# Mini_1284.net
KiCad netlist of a schematic drawn in EAGLE
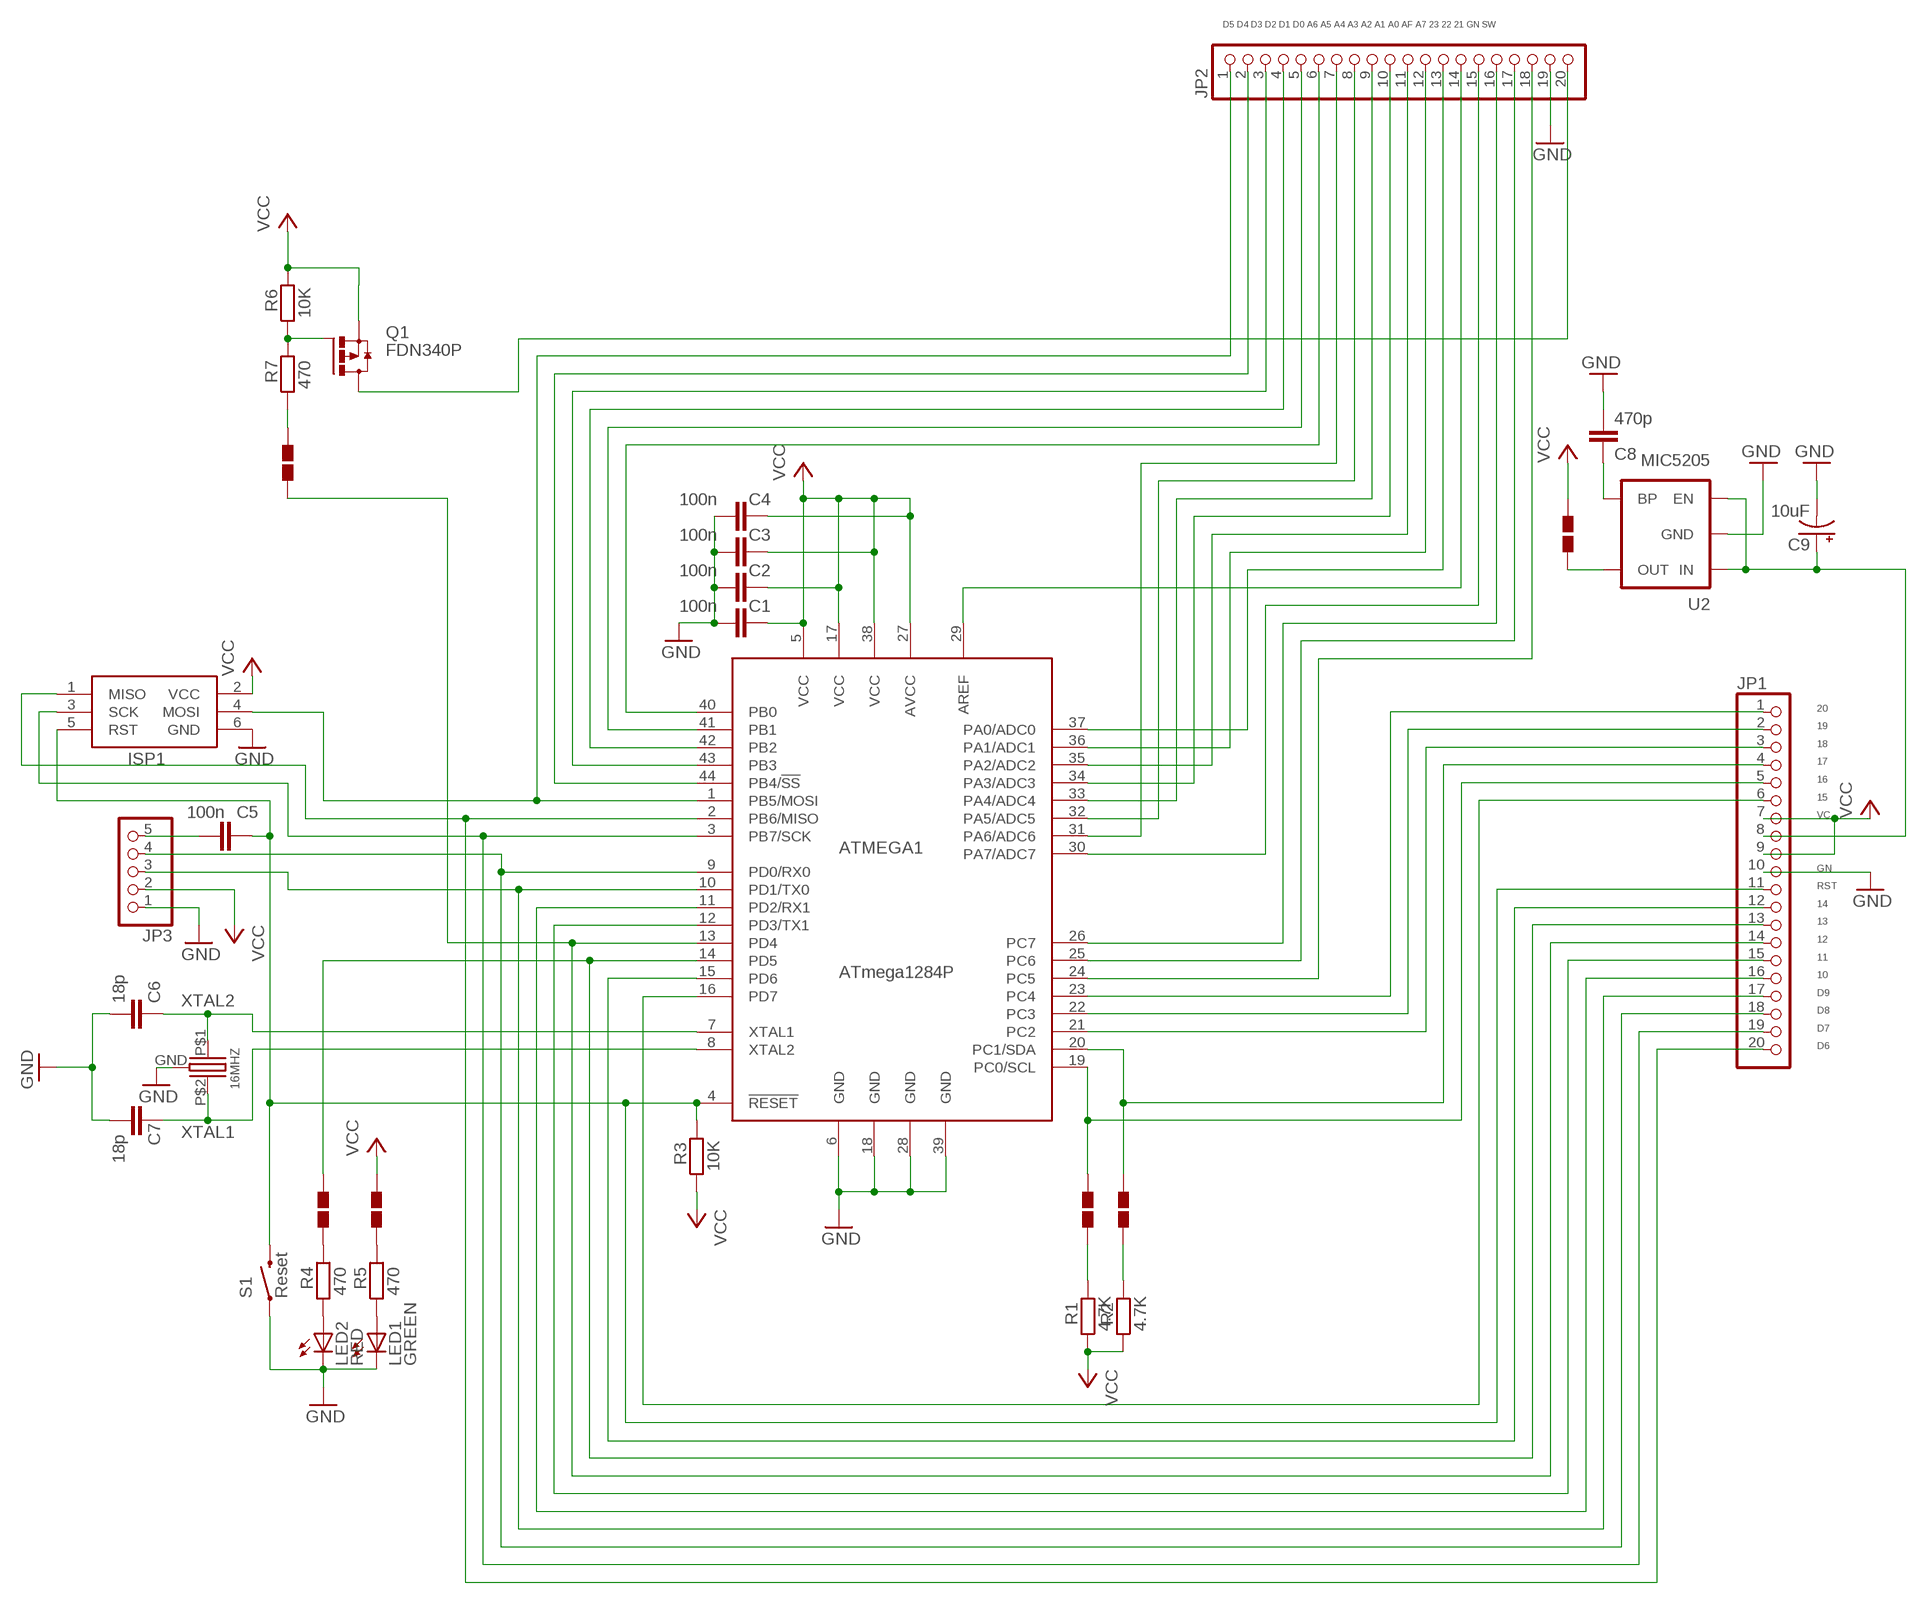
[diagram p0: schematic, sheet 1]

(export (version "E")
  (design (tool "Eeschema 10.0.6"))
  (components
    (comp (ref "16MHZ")
      (value "CX2520")
      (footprint "eagle-import:CX2520")
      (libsource (lib "eagle-import") (part "CX2520"))
    )
    (comp (ref "ATMEGA1")
      (value "ATmega1284P")
      (footprint "eagle-import:44TQFP")
      (libsource (lib "eagle-import") (part "ATMEGA164A/PA/324A/PA/644A/PA/1284/P"))
    )
    (comp (ref "C1")
      (value "100n")
      (footprint "eagle-import:C0603-ROUND")
      (libsource (lib "eagle-import") (part "C0603-ROUND"))
    )
    (comp (ref "C2")
      (value "100n")
      (footprint "eagle-import:C0603-ROUND")
      (libsource (lib "eagle-import") (part "C0603-ROUND"))
    )
    (comp (ref "C3")
      (value "100n")
      (footprint "eagle-import:C0603-ROUND")
      (libsource (lib "eagle-import") (part "C0603-ROUND"))
    )
    (comp (ref "C4")
      (value "100n")
      (footprint "eagle-import:C0603-ROUND")
      (libsource (lib "eagle-import") (part "C0603-ROUND"))
    )
    (comp (ref "C5")
      (value "100n")
      (footprint "eagle-import:C0603-ROUND")
      (libsource (lib "eagle-import") (part "C0603-ROUND"))
    )
    (comp (ref "C6")
      (value "18p")
      (footprint "eagle-import:C0603-ROUND")
      (libsource (lib "eagle-import") (part "C0603-ROUND"))
    )
    (comp (ref "C7")
      (value "18p")
      (footprint "eagle-import:C0603-ROUND")
      (libsource (lib "eagle-import") (part "C0603-ROUND"))
    )
    (comp (ref "C8")
      (value "470p")
      (footprint "eagle-import:C0603-ROUND")
      (libsource (lib "eagle-import") (part "C0603-ROUND"))
    )
    (comp (ref "C9")
      (value "10uF")
      (footprint "eagle-import:EIA3216")
      (libsource (lib "eagle-import") (part "CAP_POL1206"))
    )
    (comp (ref "ISP1")
      (value "AVRISP-6")
      (footprint "eagle-import:AVRISP")
      (libsource (lib "eagle-import") (part "AVRISP-6"))
    )
    (comp (ref "JP1")
      (value "PINHD-1X20")
      (footprint "eagle-import:1X20")
      (libsource (lib "eagle-import") (part "PINHD-1X20"))
    )
    (comp (ref "JP2")
      (value "PINHD-1X20")
      (footprint "eagle-import:1X20")
      (libsource (lib "eagle-import") (part "PINHD-1X20"))
    )
    (comp (ref "JP3")
      (value "PINHD-1X5")
      (footprint "eagle-import:1X05")
      (libsource (lib "eagle-import") (part "PINHD-1X5"))
    )
    (comp (ref "LED1")
      (value "GREEN")
      (footprint "eagle-import:CHIP-LED0805")
      (libsource (lib "eagle-import") (part "LEDCHIP-LED0805"))
    )
    (comp (ref "LED2")
      (value "RED")
      (footprint "eagle-import:CHIP-LED0805")
      (libsource (lib "eagle-import") (part "LEDCHIP-LED0805"))
    )
    (comp (ref "Q1")
      (value "FDN340P")
      (footprint "eagle-import:SUPER-SOT3")
      (libsource (lib "eagle-import") (part "FDN360P"))
    )
    (comp (ref "R1")
      (value "4.7K")
      (footprint "eagle-import:R0603-ROUND")
      (libsource (lib "eagle-import") (part "R0603-ROUND"))
    )
    (comp (ref "R2")
      (value "4.7K")
      (footprint "eagle-import:R0603-ROUND")
      (libsource (lib "eagle-import") (part "R0603-ROUND"))
    )
    (comp (ref "R3")
      (value "10K")
      (footprint "eagle-import:R0603-ROUND")
      (libsource (lib "eagle-import") (part "R0603-ROUND"))
    )
    (comp (ref "R4")
      (value "470")
      (footprint "eagle-import:R0603-ROUND")
      (libsource (lib "eagle-import") (part "R0603-ROUND"))
    )
    (comp (ref "R5")
      (value "470")
      (footprint "eagle-import:R0603-ROUND")
      (libsource (lib "eagle-import") (part "R0603-ROUND"))
    )
    (comp (ref "R6")
      (value "10K")
      (footprint "eagle-import:R0603-ROUND")
      (libsource (lib "eagle-import") (part "R0603-ROUND"))
    )
    (comp (ref "R7")
      (value "470")
      (footprint "eagle-import:R0603-ROUND")
      (libsource (lib "eagle-import") (part "R0603-ROUND"))
    )
    (comp (ref "S1")
      (value "Reset")
      (footprint "eagle-import:TACTILE-SWITCH-SMD-ALT01")
      (libsource (lib "eagle-import") (part "SWITCH-MOMENTARY-2SMD-ALT01"))
    )
    (comp (ref "U$4")
      (value "SOL-PAD-OPEN")
      (footprint "eagle-import:SOL-PAD-OPEN")
      (libsource (lib "eagle-import") (part "SOL-PAD-OPEN"))
    )
    (comp (ref "U$5")
      (value "SOL-PAD-OPEN")
      (footprint "eagle-import:SOL-PAD-OPEN")
      (libsource (lib "eagle-import") (part "SOL-PAD-OPEN"))
    )
    (comp (ref "U$8")
      (value "SOL-PAD-OPEN")
      (footprint "eagle-import:SOL-PAD-OPEN")
      (libsource (lib "eagle-import") (part "SOL-PAD-OPEN"))
    )
    (comp (ref "U$9")
      (value "SOL-PAD-OPEN")
      (footprint "eagle-import:SOL-PAD-OPEN")
      (libsource (lib "eagle-import") (part "SOL-PAD-OPEN"))
    )
    (comp (ref "U$12")
      (value "SOL-PAD-OPEN")
      (footprint "eagle-import:SOL-PAD-OPEN")
      (libsource (lib "eagle-import") (part "SOL-PAD-OPEN"))
    )
    (comp (ref "U$13")
      (value "SOL-PAD-OPEN")
      (footprint "eagle-import:SOL-PAD-OPEN")
      (libsource (lib "eagle-import") (part "SOL-PAD-OPEN"))
    )
    (comp (ref "U2")
      (value "MIC5205")
      (footprint "eagle-import:SOT23-5")
      (libsource (lib "eagle-import") (part "V_REG_LDOSMD"))
    )
  )
  (nets
    (net (code "1") (name "/XTAL1") (class "Default")
      (node (ref "16MHZ") (pin "P$2") (pinfunction "XTAL2_P$2") (pintype "bidirectional"))
      (node (ref "ATMEGA1") (pin "8") (pinfunction "XTAL2_8") (pintype "bidirectional"))
      (node (ref "C7") (pin "1") (pinfunction "1_1") (pintype "passive"))
    )
    (net (code "2") (name "/XTAL2") (class "Default")
      (node (ref "16MHZ") (pin "P$1") (pinfunction "XTAL1_P$1") (pintype "bidirectional"))
      (node (ref "ATMEGA1") (pin "7") (pinfunction "XTAL1_7") (pintype "bidirectional"))
      (node (ref "C6") (pin "1") (pinfunction "1_1") (pintype "passive"))
    )
    (net (code "3") (name "GND") (class "Default")
      (node (ref "16MHZ") (pin "GND") (pinfunction "GND_GND") (pintype "bidirectional"))
      (node (ref "ATMEGA1") (pin "18") (pinfunction "GND_18") (pintype "bidirectional"))
      (node (ref "ATMEGA1") (pin "28") (pinfunction "GND_28") (pintype "bidirectional"))
      (node (ref "ATMEGA1") (pin "39") (pinfunction "GND_39") (pintype "bidirectional"))
      (node (ref "ATMEGA1") (pin "6") (pinfunction "GND_6") (pintype "bidirectional"))
      (node (ref "C1") (pin "2") (pinfunction "2_2") (pintype "passive"))
      (node (ref "C2") (pin "2") (pinfunction "2_2") (pintype "passive"))
      (node (ref "C3") (pin "2") (pinfunction "2_2") (pintype "passive"))
      (node (ref "C4") (pin "2") (pinfunction "2_2") (pintype "passive"))
      (node (ref "C6") (pin "2") (pinfunction "2_2") (pintype "passive"))
      (node (ref "C7") (pin "2") (pinfunction "2_2") (pintype "passive"))
      (node (ref "C8") (pin "2") (pinfunction "2_2") (pintype "passive"))
      (node (ref "C9") (pin "C") (pinfunction "-_C") (pintype "passive"))
      (node (ref "ISP1") (pin "6") (pinfunction "GND_6") (pintype "power_in"))
      (node (ref "JP1") (pin "10") (pinfunction "10_10") (pintype "passive"))
      (node (ref "JP2") (pin "19") (pinfunction "19_19") (pintype "passive"))
      (node (ref "JP3") (pin "1") (pinfunction "1_1") (pintype "passive"))
      (node (ref "LED1") (pin "C") (pinfunction "C_C") (pintype "passive"))
      (node (ref "LED2") (pin "C") (pinfunction "C_C") (pintype "passive"))
      (node (ref "S1") (pin "1") (pinfunction "1_1") (pintype "passive"))
      (node (ref "S1") (pin "2") (pinfunction "1_2") (pintype "passive"))
      (node (ref "U2") (pin "2") (pinfunction "GND_2") (pintype "input"))
    )
    (net (code "4") (name "Net-(ATMEGA1-AREF)") (class "Default")
      (node (ref "ATMEGA1") (pin "29") (pinfunction "AREF_29") (pintype "bidirectional"))
      (node (ref "JP2") (pin "14") (pinfunction "14_14") (pintype "passive"))
    )
    (net (code "5") (name "Net-(ATMEGA1-PA0{slash}ADC0)") (class "Default")
      (node (ref "ATMEGA1") (pin "37") (pinfunction "PA0/ADC0_37") (pintype "bidirectional"))
      (node (ref "JP2") (pin "13") (pinfunction "13_13") (pintype "passive"))
    )
    (net (code "6") (name "Net-(ATMEGA1-PA1{slash}ADC1)") (class "Default")
      (node (ref "ATMEGA1") (pin "36") (pinfunction "PA1/ADC1_36") (pintype "bidirectional"))
      (node (ref "JP2") (pin "12") (pinfunction "12_12") (pintype "passive"))
    )
    (net (code "7") (name "Net-(ATMEGA1-PA2{slash}ADC2)") (class "Default")
      (node (ref "ATMEGA1") (pin "35") (pinfunction "PA2/ADC2_35") (pintype "bidirectional"))
      (node (ref "JP2") (pin "11") (pinfunction "11_11") (pintype "passive"))
    )
    (net (code "8") (name "Net-(ATMEGA1-PA3{slash}ADC3)") (class "Default")
      (node (ref "ATMEGA1") (pin "34") (pinfunction "PA3/ADC3_34") (pintype "bidirectional"))
      (node (ref "JP2") (pin "10") (pinfunction "10_10") (pintype "passive"))
    )
    (net (code "9") (name "Net-(ATMEGA1-PA4{slash}ADC4)") (class "Default")
      (node (ref "ATMEGA1") (pin "33") (pinfunction "PA4/ADC4_33") (pintype "bidirectional"))
      (node (ref "JP2") (pin "9") (pinfunction "9_9") (pintype "passive"))
    )
    (net (code "10") (name "Net-(ATMEGA1-PA5{slash}ADC5)") (class "Default")
      (node (ref "ATMEGA1") (pin "32") (pinfunction "PA5/ADC5_32") (pintype "bidirectional"))
      (node (ref "JP2") (pin "8") (pinfunction "8_8") (pintype "passive"))
    )
    (net (code "11") (name "Net-(ATMEGA1-PA6{slash}ADC6)") (class "Default")
      (node (ref "ATMEGA1") (pin "31") (pinfunction "PA6/ADC6_31") (pintype "bidirectional"))
      (node (ref "JP2") (pin "7") (pinfunction "7_7") (pintype "passive"))
    )
    (net (code "12") (name "Net-(ATMEGA1-PA7{slash}ADC7)") (class "Default")
      (node (ref "ATMEGA1") (pin "30") (pinfunction "PA7/ADC7_30") (pintype "bidirectional"))
      (node (ref "JP2") (pin "15") (pinfunction "15_15") (pintype "passive"))
    )
    (net (code "13") (name "Net-(ATMEGA1-PB0)") (class "Default")
      (node (ref "ATMEGA1") (pin "40") (pinfunction "PB0_40") (pintype "bidirectional"))
      (node (ref "JP2") (pin "6") (pinfunction "6_6") (pintype "passive"))
    )
    (net (code "14") (name "Net-(ATMEGA1-PB1)") (class "Default")
      (node (ref "ATMEGA1") (pin "41") (pinfunction "PB1_41") (pintype "bidirectional"))
      (node (ref "JP2") (pin "5") (pinfunction "5_5") (pintype "passive"))
    )
    (net (code "15") (name "Net-(ATMEGA1-PB2)") (class "Default")
      (node (ref "ATMEGA1") (pin "42") (pinfunction "PB2_42") (pintype "bidirectional"))
      (node (ref "JP2") (pin "4") (pinfunction "4_4") (pintype "passive"))
    )
    (net (code "16") (name "Net-(ATMEGA1-PB3)") (class "Default")
      (node (ref "ATMEGA1") (pin "43") (pinfunction "PB3_43") (pintype "bidirectional"))
      (node (ref "JP2") (pin "3") (pinfunction "3_3") (pintype "passive"))
    )
    (net (code "17") (name "Net-(ATMEGA1-PB4{slash}~{SS})") (class "Default")
      (node (ref "ATMEGA1") (pin "44") (pinfunction "PB4/~{SS}_44") (pintype "bidirectional"))
      (node (ref "JP2") (pin "2") (pinfunction "2_2") (pintype "passive"))
    )
    (net (code "18") (name "Net-(ATMEGA1-PB5{slash}MOSI)") (class "Default")
      (node (ref "ATMEGA1") (pin "1") (pinfunction "PB5/MOSI_1") (pintype "bidirectional"))
      (node (ref "ISP1") (pin "4") (pinfunction "MOSI_4") (pintype "output"))
      (node (ref "JP2") (pin "1") (pinfunction "1_1") (pintype "passive"))
    )
    (net (code "19") (name "Net-(ATMEGA1-PB6{slash}MISO)") (class "Default")
      (node (ref "ATMEGA1") (pin "2") (pinfunction "PB6/MISO_2") (pintype "bidirectional"))
      (node (ref "ISP1") (pin "1") (pinfunction "MISO_1") (pintype "input"))
      (node (ref "JP1") (pin "20") (pinfunction "20_20") (pintype "passive"))
    )
    (net (code "20") (name "Net-(ATMEGA1-PB7{slash}SCK)") (class "Default")
      (node (ref "ATMEGA1") (pin "3") (pinfunction "PB7/SCK_3") (pintype "bidirectional"))
      (node (ref "ISP1") (pin "3") (pinfunction "SCK_3") (pintype "output"))
      (node (ref "JP1") (pin "19") (pinfunction "19_19") (pintype "passive"))
    )
    (net (code "21") (name "Net-(ATMEGA1-PC0{slash}SCL)") (class "Default")
      (node (ref "ATMEGA1") (pin "19") (pinfunction "PC0/SCL_19") (pintype "bidirectional"))
      (node (ref "JP1") (pin "5") (pinfunction "5_5") (pintype "passive"))
      (node (ref "U$4") (pin "P$2") (pinfunction "2_P$2") (pintype "bidirectional"))
    )
    (net (code "22") (name "Net-(ATMEGA1-PC1{slash}SDA)") (class "Default")
      (node (ref "ATMEGA1") (pin "20") (pinfunction "PC1/SDA_20") (pintype "bidirectional"))
      (node (ref "JP1") (pin "4") (pinfunction "4_4") (pintype "passive"))
      (node (ref "U$12") (pin "P$1") (pinfunction "1_P$1") (pintype "bidirectional"))
    )
    (net (code "23") (name "Net-(ATMEGA1-PC2)") (class "Default")
      (node (ref "ATMEGA1") (pin "21") (pinfunction "PC2_21") (pintype "bidirectional"))
      (node (ref "JP1") (pin "3") (pinfunction "3_3") (pintype "passive"))
    )
    (net (code "24") (name "Net-(ATMEGA1-PC3)") (class "Default")
      (node (ref "ATMEGA1") (pin "22") (pinfunction "PC3_22") (pintype "bidirectional"))
      (node (ref "JP1") (pin "2") (pinfunction "2_2") (pintype "passive"))
    )
    (net (code "25") (name "Net-(ATMEGA1-PC4)") (class "Default")
      (node (ref "ATMEGA1") (pin "23") (pinfunction "PC4_23") (pintype "bidirectional"))
      (node (ref "JP1") (pin "1") (pinfunction "1_1") (pintype "passive"))
    )
    (net (code "26") (name "Net-(ATMEGA1-PC5)") (class "Default")
      (node (ref "ATMEGA1") (pin "24") (pinfunction "PC5_24") (pintype "bidirectional"))
      (node (ref "JP2") (pin "18") (pinfunction "18_18") (pintype "passive"))
    )
    (net (code "27") (name "Net-(ATMEGA1-PC6)") (class "Default")
      (node (ref "ATMEGA1") (pin "25") (pinfunction "PC6_25") (pintype "bidirectional"))
      (node (ref "JP2") (pin "17") (pinfunction "17_17") (pintype "passive"))
    )
    (net (code "28") (name "Net-(ATMEGA1-PC7)") (class "Default")
      (node (ref "ATMEGA1") (pin "26") (pinfunction "PC7_26") (pintype "bidirectional"))
      (node (ref "JP2") (pin "16") (pinfunction "16_16") (pintype "passive"))
    )
    (net (code "29") (name "Net-(ATMEGA1-PD0{slash}RX0)") (class "Default")
      (node (ref "ATMEGA1") (pin "9") (pinfunction "PD0/RX0_9") (pintype "bidirectional"))
      (node (ref "JP1") (pin "18") (pinfunction "18_18") (pintype "passive"))
      (node (ref "JP3") (pin "4") (pinfunction "4_4") (pintype "passive"))
    )
    (net (code "30") (name "Net-(ATMEGA1-PD1{slash}TX0)") (class "Default")
      (node (ref "ATMEGA1") (pin "10") (pinfunction "PD1/TX0_10") (pintype "bidirectional"))
      (node (ref "JP1") (pin "17") (pinfunction "17_17") (pintype "passive"))
      (node (ref "JP3") (pin "3") (pinfunction "3_3") (pintype "passive"))
    )
    (net (code "31") (name "Net-(ATMEGA1-PD2{slash}RX1)") (class "Default")
      (node (ref "ATMEGA1") (pin "11") (pinfunction "PD2/RX1_11") (pintype "bidirectional"))
      (node (ref "JP1") (pin "16") (pinfunction "16_16") (pintype "passive"))
    )
    (net (code "32") (name "Net-(ATMEGA1-PD3{slash}TX1)") (class "Default")
      (node (ref "ATMEGA1") (pin "12") (pinfunction "PD3/TX1_12") (pintype "bidirectional"))
      (node (ref "JP1") (pin "15") (pinfunction "15_15") (pintype "passive"))
    )
    (net (code "33") (name "Net-(ATMEGA1-PD4)") (class "Default")
      (node (ref "ATMEGA1") (pin "13") (pinfunction "PD4_13") (pintype "bidirectional"))
      (node (ref "JP1") (pin "14") (pinfunction "14_14") (pintype "passive"))
      (node (ref "U$5") (pin "P$1") (pinfunction "1_P$1") (pintype "bidirectional"))
    )
    (net (code "34") (name "Net-(ATMEGA1-PD5)") (class "Default")
      (node (ref "ATMEGA1") (pin "14") (pinfunction "PD5_14") (pintype "bidirectional"))
      (node (ref "JP1") (pin "13") (pinfunction "13_13") (pintype "passive"))
      (node (ref "U$9") (pin "P$2") (pinfunction "2_P$2") (pintype "bidirectional"))
    )
    (net (code "35") (name "Net-(ATMEGA1-PD6)") (class "Default")
      (node (ref "ATMEGA1") (pin "15") (pinfunction "PD6_15") (pintype "bidirectional"))
      (node (ref "JP1") (pin "12") (pinfunction "12_12") (pintype "passive"))
    )
    (net (code "36") (name "Net-(ATMEGA1-PD7)") (class "Default")
      (node (ref "ATMEGA1") (pin "16") (pinfunction "PD7_16") (pintype "bidirectional"))
      (node (ref "JP1") (pin "6") (pinfunction "6_6") (pintype "passive"))
    )
    (net (code "37") (name "Net-(ATMEGA1-~{RESET})") (class "Default")
      (node (ref "ATMEGA1") (pin "4") (pinfunction "~{RESET}_4") (pintype "bidirectional"))
      (node (ref "C5") (pin "1") (pinfunction "1_1") (pintype "passive"))
      (node (ref "ISP1") (pin "5") (pinfunction "RST_5") (pintype "output"))
      (node (ref "JP1") (pin "11") (pinfunction "11_11") (pintype "passive"))
      (node (ref "R3") (pin "2") (pinfunction "2_2") (pintype "passive"))
      (node (ref "S1") (pin "3") (pinfunction "2_3") (pintype "passive"))
      (node (ref "S1") (pin "4") (pinfunction "2_4") (pintype "passive"))
    )
    (net (code "38") (name "Net-(C5-Pad2)") (class "Default")
      (node (ref "C5") (pin "2") (pinfunction "2_2") (pintype "passive"))
      (node (ref "JP3") (pin "5") (pinfunction "5_5") (pintype "passive"))
    )
    (net (code "39") (name "Net-(C9-+)") (class "Default")
      (node (ref "C9") (pin "A") (pinfunction "+_A") (pintype "passive"))
      (node (ref "JP1") (pin "8") (pinfunction "8_8") (pintype "passive"))
      (node (ref "U2") (pin "1") (pinfunction "IN_1") (pintype "input"))
      (node (ref "U2") (pin "3") (pinfunction "EN_3") (pintype "input"))
    )
    (net (code "40") (name "Net-(LED1-PadA)") (class "Default")
      (node (ref "LED1") (pin "A") (pinfunction "A_A") (pintype "passive"))
      (node (ref "R5") (pin "1") (pinfunction "1_1") (pintype "passive"))
    )
    (net (code "41") (name "Net-(LED2-PadA)") (class "Default")
      (node (ref "LED2") (pin "A") (pinfunction "A_A") (pintype "passive"))
      (node (ref "R4") (pin "1") (pinfunction "1_1") (pintype "passive"))
    )
    (net (code "42") (name "Net-(Q1-D)") (class "Default")
      (node (ref "JP2") (pin "20") (pinfunction "20_20") (pintype "passive"))
      (node (ref "Q1") (pin "3") (pinfunction "D_3") (pintype "passive"))
    )
    (net (code "43") (name "Net-(Q1-G)") (class "Default")
      (node (ref "Q1") (pin "1") (pinfunction "G_1") (pintype "passive"))
      (node (ref "R6") (pin "1") (pinfunction "1_1") (pintype "passive"))
      (node (ref "R7") (pin "2") (pinfunction "2_2") (pintype "passive"))
    )
    (net (code "44") (name "Net-(U$4-1)") (class "Default")
      (node (ref "R1") (pin "2") (pinfunction "2_2") (pintype "passive"))
      (node (ref "U$4") (pin "P$1") (pinfunction "1_P$1") (pintype "bidirectional"))
    )
    (net (code "45") (name "Net-(U$5-2)") (class "Default")
      (node (ref "R7") (pin "1") (pinfunction "1_1") (pintype "passive"))
      (node (ref "U$5") (pin "P$2") (pinfunction "2_P$2") (pintype "bidirectional"))
    )
    (net (code "46") (name "Net-(U$8-1)") (class "Default")
      (node (ref "R5") (pin "2") (pinfunction "2_2") (pintype "passive"))
      (node (ref "U$8") (pin "P$1") (pinfunction "1_P$1") (pintype "bidirectional"))
    )
    (net (code "47") (name "Net-(U$9-1)") (class "Default")
      (node (ref "R4") (pin "2") (pinfunction "2_2") (pintype "passive"))
      (node (ref "U$9") (pin "P$1") (pinfunction "1_P$1") (pintype "bidirectional"))
    )
    (net (code "48") (name "Net-(U$12-2)") (class "Default")
      (node (ref "R2") (pin "2") (pinfunction "2_2") (pintype "passive"))
      (node (ref "U$12") (pin "P$2") (pinfunction "2_P$2") (pintype "bidirectional"))
    )
    (net (code "49") (name "Net-(U$13-2)") (class "Default")
      (node (ref "U$13") (pin "P$2") (pinfunction "2_P$2") (pintype "bidirectional"))
      (node (ref "U2") (pin "5") (pinfunction "OUT_5") (pintype "passive"))
    )
    (net (code "50") (name "Net-(U2-BP)") (class "Default")
      (node (ref "C8") (pin "1") (pinfunction "1_1") (pintype "passive"))
      (node (ref "U2") (pin "4") (pinfunction "BP_4") (pintype "input"))
    )
    (net (code "51") (name "VCC") (class "Default")
      (node (ref "ATMEGA1") (pin "17") (pinfunction "VCC_17") (pintype "bidirectional"))
      (node (ref "ATMEGA1") (pin "27") (pinfunction "AVCC_27") (pintype "bidirectional"))
      (node (ref "ATMEGA1") (pin "38") (pinfunction "VCC_38") (pintype "bidirectional"))
      (node (ref "ATMEGA1") (pin "5") (pinfunction "VCC_5") (pintype "bidirectional"))
      (node (ref "C1") (pin "1") (pinfunction "1_1") (pintype "passive"))
      (node (ref "C2") (pin "1") (pinfunction "1_1") (pintype "passive"))
      (node (ref "C3") (pin "1") (pinfunction "1_1") (pintype "passive"))
      (node (ref "C4") (pin "1") (pinfunction "1_1") (pintype "passive"))
      (node (ref "ISP1") (pin "2") (pinfunction "VCC_2") (pintype "power_in"))
      (node (ref "JP1") (pin "7") (pinfunction "7_7") (pintype "passive"))
      (node (ref "JP1") (pin "9") (pinfunction "9_9") (pintype "passive"))
      (node (ref "JP3") (pin "2") (pinfunction "2_2") (pintype "passive"))
      (node (ref "Q1") (pin "2") (pinfunction "S_2") (pintype "passive"))
      (node (ref "R1") (pin "1") (pinfunction "1_1") (pintype "passive"))
      (node (ref "R2") (pin "1") (pinfunction "1_1") (pintype "passive"))
      (node (ref "R3") (pin "1") (pinfunction "1_1") (pintype "passive"))
      (node (ref "R6") (pin "2") (pinfunction "2_2") (pintype "passive"))
      (node (ref "U$13") (pin "P$1") (pinfunction "1_P$1") (pintype "bidirectional"))
      (node (ref "U$8") (pin "P$2") (pinfunction "2_P$2") (pintype "bidirectional"))
    )
  )
)
